# switch_LED.net
KiCad netlist of a schematic drawn in EAGLE
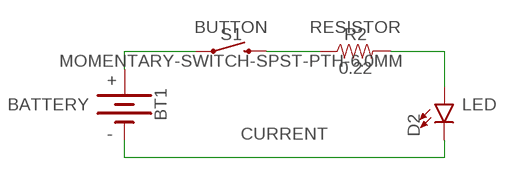
[diagram p0: schematic, sheet 1]

(export (version "E")
  (design (tool "Eeschema 10.0.6"))
  (components
    (comp (ref "BT1")
      (value "BATTERY-9V")
      (footprint "eagle-import:BATTCON_9V")
      (libsource (lib "eagle-import") (part "BATTERY-9V"))
    )
    (comp (ref "D2")
      (value "LED5MM")
      (footprint "eagle-import:LED_5MM")
      (libsource (lib "eagle-import") (part "LED5MM"))
    )
    (comp (ref "R2")
      (value "0.22")
      (footprint "eagle-import:0805")
      (libsource (lib "eagle-import") (part "0.22OHM-0805-1/4W-1%"))
    )
    (comp (ref "S1")
      (value "MOMENTARY-SWITCH-SPST-PTH-6.0MM")
      (footprint "eagle-import:TACTILE_SWITCH_PTH_6.0MM")
      (libsource (lib "eagle-import") (part "MOMENTARY-SWITCH-SPST-PTH-6.0MM"))
    )
  )
  (nets
    (net (code "1") (name "Net-(BT1-Pad+)") (class "Default")
      (node (ref "BT1") (pin "+") (pinfunction "+_+") (pintype "power_in"))
      (node (ref "S1") (pin "1") (pinfunction "1_1") (pintype "passive"))
    )
    (net (code "2") (name "Net-(D2-C)") (class "Default")
      (node (ref "BT1") (pin "-") (pinfunction "-_-") (pintype "power_in"))
      (node (ref "D2") (pin "K") (pinfunction "C_K") (pintype "passive"))
    )
    (net (code "3") (name "Net-(D2-PadA)") (class "Default")
      (node (ref "D2") (pin "A") (pinfunction "A_A") (pintype "passive"))
      (node (ref "R2") (pin "2") (pinfunction "2_2") (pintype "passive"))
    )
    (net (code "4") (name "Net-(S1-2)") (class "Default")
      (node (ref "R2") (pin "1") (pinfunction "1_1") (pintype "passive"))
      (node (ref "S1") (pin "3") (pinfunction "2_3") (pintype "passive"))
    )
  )
)
